# Qwiic_USB_Bridge_ATSAMD21G.net
KiCad netlist of a schematic drawn in EAGLE
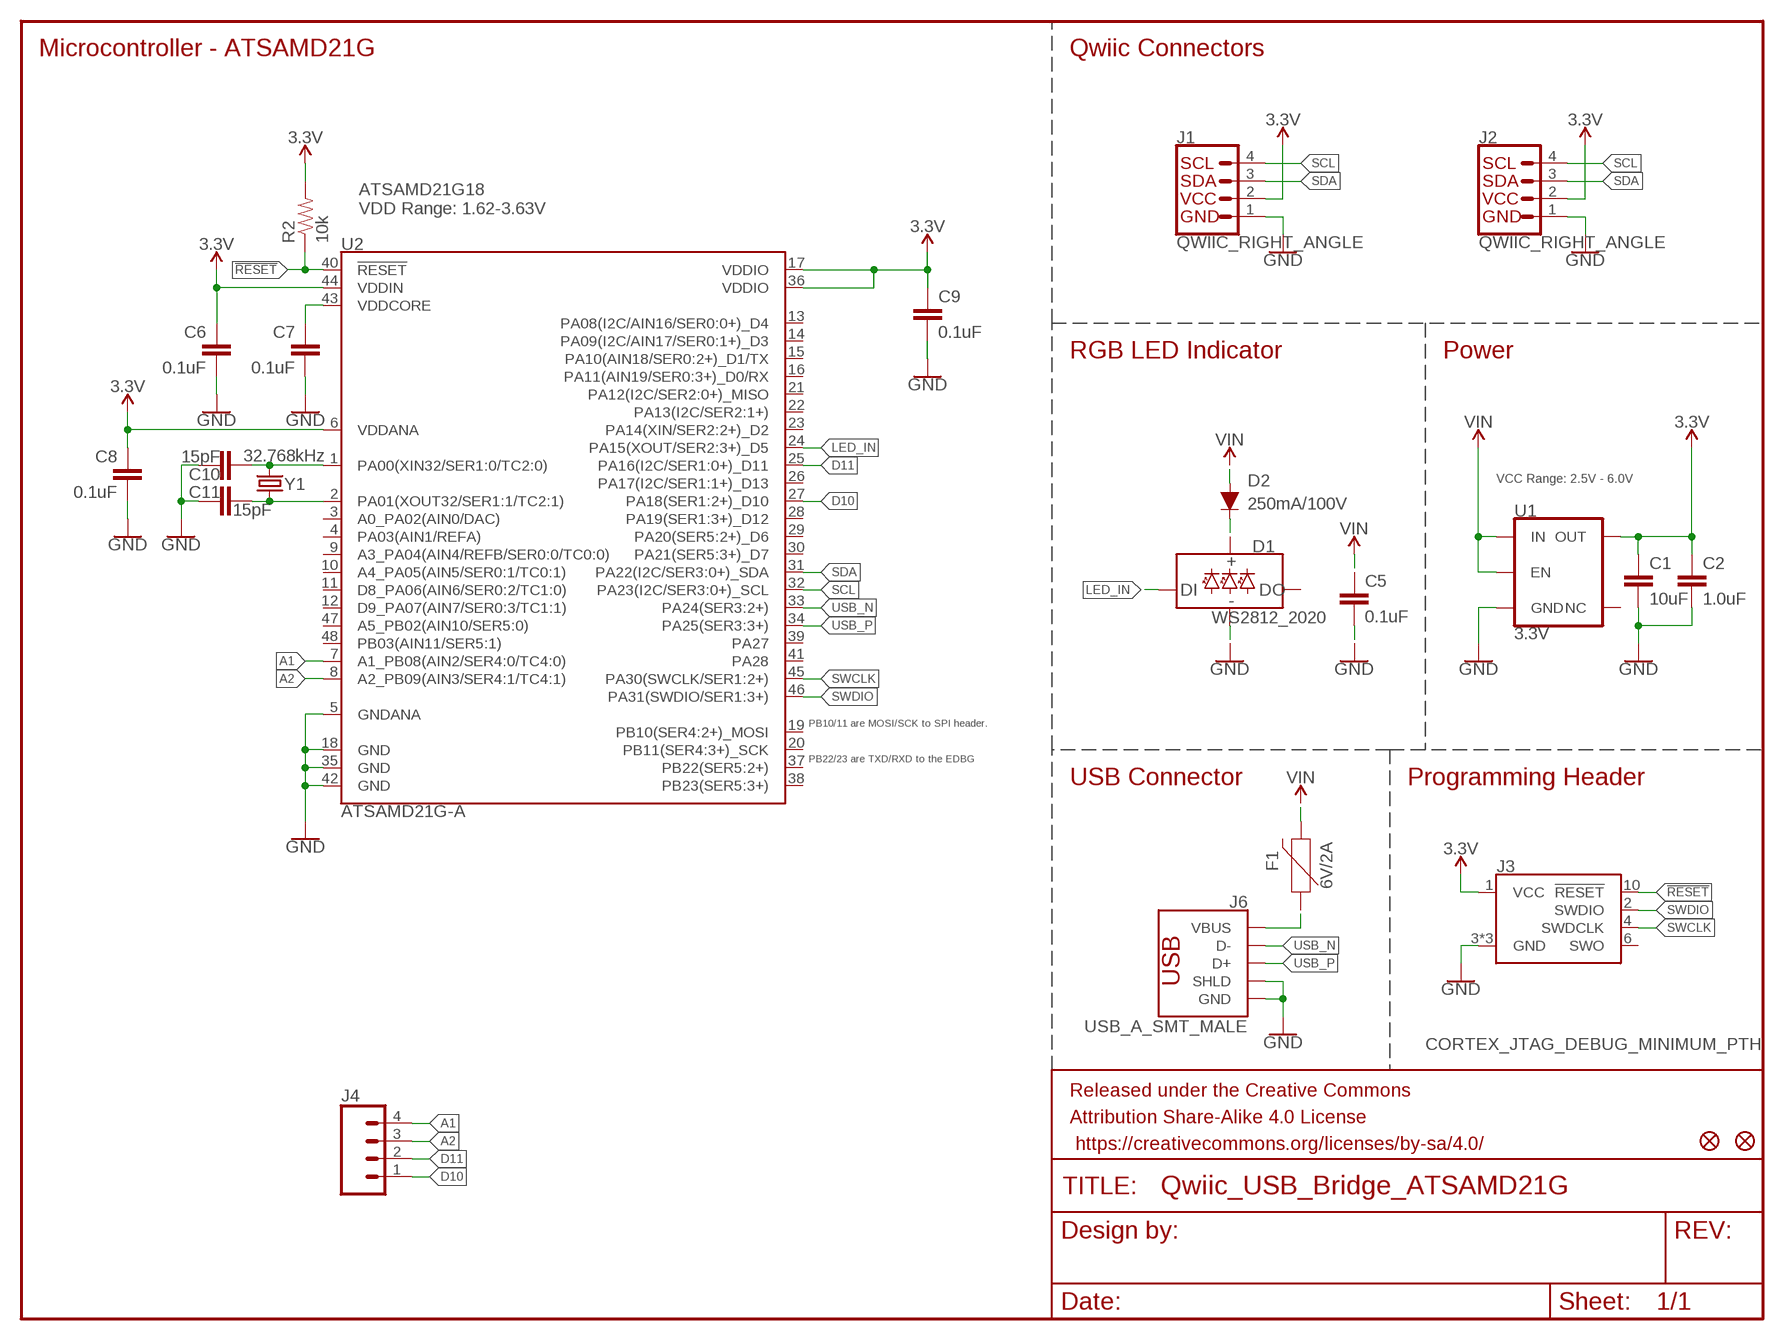
[diagram p0: schematic, sheet 1]

(export (version "E")
  (design (tool "Eeschema 10.0.6"))
  (components
    (comp (ref "C1")
      (value "10uF")
      (footprint "eagle-import:0603")
      (libsource (lib "eagle-import") (part "10UF-0603-6.3V-20%"))
    )
    (comp (ref "C2")
      (value "1.0uF")
      (footprint "eagle-import:0603")
      (libsource (lib "eagle-import") (part "1.0UF-0603-16V-10%"))
    )
    (comp (ref "C5")
      (value "0.1uF")
      (footprint "eagle-import:0603")
      (libsource (lib "eagle-import") (part "0.1UF-0603-25V-(+80/-20%)"))
    )
    (comp (ref "C6")
      (value "0.1uF")
      (footprint "eagle-import:0603")
      (libsource (lib "eagle-import") (part "0.1UF-0603-25V-(+80/-20%)"))
    )
    (comp (ref "C7")
      (value "0.1uF")
      (footprint "eagle-import:0603")
      (libsource (lib "eagle-import") (part "0.1UF-0603-25V-(+80/-20%)"))
    )
    (comp (ref "C8")
      (value "0.1uF")
      (footprint "eagle-import:0603")
      (libsource (lib "eagle-import") (part "0.1UF-0603-25V-(+80/-20%)"))
    )
    (comp (ref "C9")
      (value "0.1uF")
      (footprint "eagle-import:0603")
      (libsource (lib "eagle-import") (part "0.1UF-0603-25V-(+80/-20%)"))
    )
    (comp (ref "C10")
      (value "15pF")
      (footprint "eagle-import:0603")
      (libsource (lib "eagle-import") (part "15PF-0603-50V-5%"))
    )
    (comp (ref "C11")
      (value "15pF")
      (footprint "eagle-import:0603")
      (libsource (lib "eagle-import") (part "15PF-0603-50V-5%"))
    )
    (comp (ref "D1")
      (value "WS2812_2020")
      (footprint "eagle-import:WS2812-2020")
      (libsource (lib "eagle-import") (part "WS2812_2020"))
    )
    (comp (ref "D2")
      (value "250mA/100V")
      (footprint "eagle-import:SOD-323")
      (libsource (lib "eagle-import") (part "DIODE-BAS16J"))
    )
    (comp (ref "F1")
      (value "6V/2A")
      (footprint "eagle-import:1210")
      (libsource (lib "eagle-import") (part "PPTC_6V2A"))
    )
    (comp (ref "FD1")
      (value "FIDUCIALUFIDUCIAL")
      (footprint "eagle-import:FIDUCIAL-MICRO")
      (libsource (lib "eagle-import") (part "FIDUCIALUFIDUCIAL"))
    )
    (comp (ref "FD2")
      (value "FIDUCIALUFIDUCIAL")
      (footprint "eagle-import:FIDUCIAL-MICRO")
      (libsource (lib "eagle-import") (part "FIDUCIALUFIDUCIAL"))
    )
    (comp (ref "FRAME2")
      (value "FRAME-LETTER")
      (footprint "eagle-import:CREATIVE_COMMONS")
      (libsource (lib "eagle-import") (part "FRAME-LETTER"))
    )
    (comp (ref "J1")
      (value "QWIIC_RIGHT_ANGLE")
      (footprint "eagle-import:JST04_1MM_RA")
      (libsource (lib "eagle-import") (part "QWIIC_CONNECTORJS-1MM"))
    )
    (comp (ref "J2")
      (value "QWIIC_RIGHT_ANGLE")
      (footprint "eagle-import:JST04_1MM_RA")
      (libsource (lib "eagle-import") (part "QWIIC_CONNECTORJS-1MM"))
    )
    (comp (ref "J3")
      (value "CORTEX_JTAG_DEBUG_MINIMUM_PTH")
      (footprint "eagle-import:2X5-PTH-1.27MM")
      (libsource (lib "eagle-import") (part "CORTEX_JTAG_DEBUG_MINIMUM_PTH"))
    )
    (comp (ref "J4")
      (value "CONN_041X04_NO_SILK")
      (footprint "eagle-import:1X04_NO_SILK")
      (libsource (lib "eagle-import") (part "CONN_041X04_NO_SILK"))
    )
    (comp (ref "J6")
      (value "USB_A_SMT_MALE")
      (footprint "eagle-import:USB-A-SMT-MALE")
      (libsource (lib "eagle-import") (part "USB_A_SMT_MALE"))
    )
    (comp (ref "R2")
      (value "10k")
      (footprint "eagle-import:0603")
      (libsource (lib "eagle-import") (part "10KOHM-0603-1/10W-1%"))
    )
    (comp (ref "U1")
      (value "3.3V")
      (footprint "eagle-import:SOT23-5")
      (libsource (lib "eagle-import") (part "V_REG_AP2112K-3.3V"))
    )
    (comp (ref "U2")
      (value "ATSAMD21G-A")
      (footprint "eagle-import:TQFP-48")
      (libsource (lib "eagle-import") (part "ATSAMD21G-A"))
    )
    (comp (ref "Y1")
      (value "32.768kHz")
      (footprint "eagle-import:CRYSTAL-SMD-3.2X1.5MM")
      (libsource (lib "eagle-import") (part "CRYSTAL-32.768KHZSMD-3.2X1.5"))
    )
  )
  (nets
    (net (code "1") (name "/~{RESET}") (class "Default")
      (node (ref "J3") (pin "10") (pinfunction "~{RESET}_10") (pintype "bidirectional"))
      (node (ref "R2") (pin "1") (pinfunction "1_1") (pintype "passive"))
      (node (ref "U2") (pin "40") (pinfunction "~{RESET}_40") (pintype "bidirectional"))
    )
    (net (code "2") (name "3.3V") (class "Default")
      (node (ref "C1") (pin "1") (pinfunction "1_1") (pintype "passive"))
      (node (ref "C2") (pin "1") (pinfunction "1_1") (pintype "passive"))
      (node (ref "C6") (pin "1") (pinfunction "1_1") (pintype "passive"))
      (node (ref "C8") (pin "1") (pinfunction "1_1") (pintype "passive"))
      (node (ref "C9") (pin "1") (pinfunction "1_1") (pintype "passive"))
      (node (ref "J1") (pin "2") (pinfunction "2_2") (pintype "power_in"))
      (node (ref "J2") (pin "2") (pinfunction "2_2") (pintype "power_in"))
      (node (ref "J3") (pin "1") (pinfunction "VCC_1") (pintype "bidirectional"))
      (node (ref "R2") (pin "2") (pinfunction "2_2") (pintype "passive"))
      (node (ref "U1") (pin "5") (pinfunction "OUT_5") (pintype "passive"))
      (node (ref "U2") (pin "17") (pinfunction "VDDIO_17") (pintype "bidirectional"))
      (node (ref "U2") (pin "36") (pinfunction "VDDIO_36") (pintype "bidirectional"))
      (node (ref "U2") (pin "44") (pinfunction "VDDIN_44") (pintype "bidirectional"))
      (node (ref "U2") (pin "6") (pinfunction "VDDANA_6") (pintype "bidirectional"))
    )
    (net (code "3") (name "A1") (class "Default")
      (node (ref "J4") (pin "4") (pinfunction "4_4") (pintype "passive"))
      (node (ref "U2") (pin "7") (pinfunction "A1_PB08(AIN2/SER4:0/TC4:0)_7") (pintype "bidirectional"))
    )
    (net (code "4") (name "A2") (class "Default")
      (node (ref "J4") (pin "3") (pinfunction "3_3") (pintype "passive"))
      (node (ref "U2") (pin "8") (pinfunction "A2_PB09(AIN3/SER4:1/TC4:1)_8") (pintype "bidirectional"))
    )
    (net (code "5") (name "D10") (class "Default")
      (node (ref "J4") (pin "1") (pinfunction "1_1") (pintype "passive"))
      (node (ref "U2") (pin "27") (pinfunction "PA18(SER1:2+)_D10_27") (pintype "bidirectional"))
    )
    (net (code "6") (name "D11") (class "Default")
      (node (ref "J4") (pin "2") (pinfunction "2_2") (pintype "passive"))
      (node (ref "U2") (pin "25") (pinfunction "PA16(I2C/SER1:0+)_D11_25") (pintype "bidirectional"))
    )
    (net (code "7") (name "GND") (class "Default")
      (node (ref "C1") (pin "2") (pinfunction "2_2") (pintype "passive"))
      (node (ref "C10") (pin "1") (pinfunction "1_1") (pintype "passive"))
      (node (ref "C11") (pin "2") (pinfunction "2_2") (pintype "passive"))
      (node (ref "C2") (pin "2") (pinfunction "2_2") (pintype "passive"))
      (node (ref "C5") (pin "2") (pinfunction "2_2") (pintype "passive"))
      (node (ref "C6") (pin "2") (pinfunction "2_2") (pintype "passive"))
      (node (ref "C7") (pin "2") (pinfunction "2_2") (pintype "passive"))
      (node (ref "C8") (pin "2") (pinfunction "2_2") (pintype "passive"))
      (node (ref "C9") (pin "2") (pinfunction "2_2") (pintype "passive"))
      (node (ref "D1") (pin "GND") (pinfunction "GND_GND") (pintype "bidirectional"))
      (node (ref "J1") (pin "1") (pinfunction "1_1") (pintype "power_in"))
      (node (ref "J2") (pin "1") (pinfunction "1_1") (pintype "power_in"))
      (node (ref "J3") (pin "3") (pinfunction "GND_3") (pintype "bidirectional"))
      (node (ref "J3") (pin "5") (pinfunction "GND_5") (pintype "bidirectional"))
      (node (ref "J3") (pin "9") (pinfunction "GND_9") (pintype "bidirectional"))
      (node (ref "J6") (pin "GND1") (pinfunction "GND_GND1") (pintype "power_in"))
      (node (ref "J6") (pin "SHLD1") (pinfunction "SHLD_SHLD1") (pintype "bidirectional"))
      (node (ref "J6") (pin "SHLD2") (pinfunction "SHLD_SHLD2") (pintype "bidirectional"))
      (node (ref "U1") (pin "2") (pinfunction "GND_2") (pintype "input"))
      (node (ref "U2") (pin "18") (pinfunction "GND_18") (pintype "bidirectional"))
      (node (ref "U2") (pin "35") (pinfunction "GND_35") (pintype "bidirectional"))
      (node (ref "U2") (pin "42") (pinfunction "GND_42") (pintype "bidirectional"))
      (node (ref "U2") (pin "5") (pinfunction "GNDANA_5") (pintype "bidirectional"))
    )
    (net (code "8") (name "LED_IN") (class "Default")
      (node (ref "D1") (pin "DI") (pinfunction "DI_DI") (pintype "bidirectional"))
      (node (ref "U2") (pin "24") (pinfunction "PA15(XOUT/SER2:3+)_D5_24") (pintype "bidirectional"))
    )
    (net (code "9") (name "Net-(D1-PadVCC)") (class "Default")
      (node (ref "D1") (pin "VCC") (pinfunction "VCC_VCC") (pintype "bidirectional"))
      (node (ref "D2") (pin "C") (pinfunction "C_C") (pintype "passive"))
    )
    (net (code "10") (name "Net-(J6-VBUS)") (class "Default")
      (node (ref "F1") (pin "1") (pinfunction "1_1") (pintype "bidirectional"))
      (node (ref "J6") (pin "VBUS1") (pinfunction "VBUS_VBUS1") (pintype "power_in"))
    )
    (net (code "11") (name "Net-(U2-PA00(XIN32{slash}SER1:0{slash}TC2:0))") (class "Default")
      (node (ref "C10") (pin "2") (pinfunction "2_2") (pintype "passive"))
      (node (ref "U2") (pin "1") (pinfunction "PA00(XIN32/SER1:0/TC2:0)_1") (pintype "bidirectional"))
      (node (ref "Y1") (pin "P$2") (pinfunction "2_P$2") (pintype "passive"))
    )
    (net (code "12") (name "Net-(U2-PA01(XOUT32{slash}SER1:1{slash}TC2:1))") (class "Default")
      (node (ref "C11") (pin "1") (pinfunction "1_1") (pintype "passive"))
      (node (ref "U2") (pin "2") (pinfunction "PA01(XOUT32/SER1:1/TC2:1)_2") (pintype "bidirectional"))
      (node (ref "Y1") (pin "P$1") (pinfunction "1_P$1") (pintype "passive"))
    )
    (net (code "13") (name "Net-(U2-VDDCORE)") (class "Default")
      (node (ref "C7") (pin "1") (pinfunction "1_1") (pintype "passive"))
      (node (ref "U2") (pin "43") (pinfunction "VDDCORE_43") (pintype "bidirectional"))
    )
    (net (code "14") (name "SCL") (class "Default")
      (node (ref "J1") (pin "4") (pinfunction "4_4") (pintype "passive"))
      (node (ref "J2") (pin "4") (pinfunction "4_4") (pintype "passive"))
      (node (ref "U2") (pin "32") (pinfunction "PA23(I2C/SER3:0+)_SCL_32") (pintype "bidirectional"))
    )
    (net (code "15") (name "SDA") (class "Default")
      (node (ref "J1") (pin "3") (pinfunction "3_3") (pintype "passive"))
      (node (ref "J2") (pin "3") (pinfunction "3_3") (pintype "passive"))
      (node (ref "U2") (pin "31") (pinfunction "PA22(I2C/SER3:0+)_SDA_31") (pintype "bidirectional"))
    )
    (net (code "16") (name "SWCLK") (class "Default")
      (node (ref "J3") (pin "4") (pinfunction "SWDCLK_4") (pintype "bidirectional"))
      (node (ref "U2") (pin "45") (pinfunction "PA30(SWCLK/SER1:2+)_45") (pintype "bidirectional"))
    )
    (net (code "17") (name "SWDIO") (class "Default")
      (node (ref "J3") (pin "2") (pinfunction "SWDIO_2") (pintype "bidirectional"))
      (node (ref "U2") (pin "46") (pinfunction "PA31(SWDIO/SER1:3+)_46") (pintype "bidirectional"))
    )
    (net (code "18") (name "USB_N") (class "Default")
      (node (ref "J6") (pin "D-1") (pinfunction "D-_D-1") (pintype "bidirectional"))
      (node (ref "U2") (pin "33") (pinfunction "PA24(SER3:2+)_33") (pintype "bidirectional"))
    )
    (net (code "19") (name "USB_P") (class "Default")
      (node (ref "J6") (pin "D+1") (pinfunction "D+_D+1") (pintype "bidirectional"))
      (node (ref "U2") (pin "34") (pinfunction "PA25(SER3:3+)_34") (pintype "bidirectional"))
    )
    (net (code "20") (name "VIN") (class "Default")
      (node (ref "C5") (pin "1") (pinfunction "1_1") (pintype "passive"))
      (node (ref "D2") (pin "A") (pinfunction "A_A") (pintype "passive"))
      (node (ref "F1") (pin "2") (pinfunction "2_2") (pintype "bidirectional"))
      (node (ref "U1") (pin "1") (pinfunction "IN_1") (pintype "input"))
      (node (ref "U1") (pin "3") (pinfunction "EN_3") (pintype "input"))
    )
    (net (code "21") (name "unconnected-(D1-PadDO)") (class "Default")
      (node (ref "D1") (pin "DO") (pinfunction "DO_DO") (pintype "bidirectional"))
    )
    (net (code "22") (name "unconnected-(J3-SWO-Pad6)") (class "Default")
      (node (ref "J3") (pin "6") (pinfunction "SWO_6") (pintype "bidirectional"))
    )
    (net (code "23") (name "unconnected-(U1-NC-Pad4)") (class "Default")
      (node (ref "U1") (pin "4") (pinfunction "NC_4") (pintype "no_connect"))
    )
    (net (code "24") (name "unconnected-(U2-A0_PA02(AIN0{slash}DAC)-Pad3)") (class "Default")
      (node (ref "U2") (pin "3") (pinfunction "A0_PA02(AIN0/DAC)_3") (pintype "bidirectional"))
    )
    (net (code "25") (name "unconnected-(U2-A3_PA04(AIN4{slash}REFB{slash}SER0:0{slash}TC0:0)-Pad9)") (class "Default")
      (node (ref "U2") (pin "9") (pinfunction "A3_PA04(AIN4/REFB/SER0:0/TC0:0)_9") (pintype "bidirectional"))
    )
    (net (code "26") (name "unconnected-(U2-A4_PA05(AIN5{slash}SER0:1{slash}TC0:1)-Pad10)") (class "Default")
      (node (ref "U2") (pin "10") (pinfunction "A4_PA05(AIN5/SER0:1/TC0:1)_10") (pintype "bidirectional"))
    )
    (net (code "27") (name "unconnected-(U2-A5_PB02(AIN10{slash}SER5:0)-Pad47)") (class "Default")
      (node (ref "U2") (pin "47") (pinfunction "A5_PB02(AIN10/SER5:0)_47") (pintype "bidirectional"))
    )
    (net (code "28") (name "unconnected-(U2-D8_PA06(AIN6{slash}SER0:2{slash}TC1:0)-Pad11)") (class "Default")
      (node (ref "U2") (pin "11") (pinfunction "D8_PA06(AIN6/SER0:2/TC1:0)_11") (pintype "bidirectional"))
    )
    (net (code "29") (name "unconnected-(U2-D9_PA07(AIN7{slash}SER0:3{slash}TC1:1)-Pad12)") (class "Default")
      (node (ref "U2") (pin "12") (pinfunction "D9_PA07(AIN7/SER0:3/TC1:1)_12") (pintype "bidirectional"))
    )
    (net (code "30") (name "unconnected-(U2-PA03(AIN1{slash}REFA)-Pad4)") (class "Default")
      (node (ref "U2") (pin "4") (pinfunction "PA03(AIN1/REFA)_4") (pintype "bidirectional"))
    )
    (net (code "31") (name "unconnected-(U2-PA08(I2C{slash}AIN16{slash}SER0:0+)_D4-Pad13)") (class "Default")
      (node (ref "U2") (pin "13") (pinfunction "PA08(I2C/AIN16/SER0:0+)_D4_13") (pintype "bidirectional"))
    )
    (net (code "32") (name "unconnected-(U2-PA09(I2C{slash}AIN17{slash}SER0:1+)_D3-Pad14)") (class "Default")
      (node (ref "U2") (pin "14") (pinfunction "PA09(I2C/AIN17/SER0:1+)_D3_14") (pintype "bidirectional"))
    )
    (net (code "33") (name "unconnected-(U2-PA10(AIN18{slash}SER0:2+)_D1{slash}TX-Pad15)") (class "Default")
      (node (ref "U2") (pin "15") (pinfunction "PA10(AIN18/SER0:2+)_D1/TX_15") (pintype "bidirectional"))
    )
    (net (code "34") (name "unconnected-(U2-PA11(AIN19{slash}SER0:3+)_D0{slash}RX-Pad16)") (class "Default")
      (node (ref "U2") (pin "16") (pinfunction "PA11(AIN19/SER0:3+)_D0/RX_16") (pintype "bidirectional"))
    )
    (net (code "35") (name "unconnected-(U2-PA12(I2C{slash}SER2:0+)_MISO-Pad21)") (class "Default")
      (node (ref "U2") (pin "21") (pinfunction "PA12(I2C/SER2:0+)_MISO_21") (pintype "bidirectional"))
    )
    (net (code "36") (name "unconnected-(U2-PA13(I2C{slash}SER2:1+)-Pad22)") (class "Default")
      (node (ref "U2") (pin "22") (pinfunction "PA13(I2C/SER2:1+)_22") (pintype "bidirectional"))
    )
    (net (code "37") (name "unconnected-(U2-PA14(XIN{slash}SER2:2+)_D2-Pad23)") (class "Default")
      (node (ref "U2") (pin "23") (pinfunction "PA14(XIN/SER2:2+)_D2_23") (pintype "bidirectional"))
    )
    (net (code "38") (name "unconnected-(U2-PA17(I2C{slash}SER1:1+)_D13-Pad26)") (class "Default")
      (node (ref "U2") (pin "26") (pinfunction "PA17(I2C/SER1:1+)_D13_26") (pintype "bidirectional"))
    )
    (net (code "39") (name "unconnected-(U2-PA19(SER1:3+)_D12-Pad28)") (class "Default")
      (node (ref "U2") (pin "28") (pinfunction "PA19(SER1:3+)_D12_28") (pintype "bidirectional"))
    )
    (net (code "40") (name "unconnected-(U2-PA20(SER5:2+)_D6-Pad29)") (class "Default")
      (node (ref "U2") (pin "29") (pinfunction "PA20(SER5:2+)_D6_29") (pintype "bidirectional"))
    )
    (net (code "41") (name "unconnected-(U2-PA21(SER5:3+)_D7-Pad30)") (class "Default")
      (node (ref "U2") (pin "30") (pinfunction "PA21(SER5:3+)_D7_30") (pintype "bidirectional"))
    )
    (net (code "42") (name "unconnected-(U2-PA27-Pad39)") (class "Default")
      (node (ref "U2") (pin "39") (pinfunction "PA27_39") (pintype "bidirectional"))
    )
    (net (code "43") (name "unconnected-(U2-PA28-Pad41)") (class "Default")
      (node (ref "U2") (pin "41") (pinfunction "PA28_41") (pintype "bidirectional"))
    )
    (net (code "44") (name "unconnected-(U2-PB03(AIN11{slash}SER5:1)-Pad48)") (class "Default")
      (node (ref "U2") (pin "48") (pinfunction "PB03(AIN11/SER5:1)_48") (pintype "bidirectional"))
    )
    (net (code "45") (name "unconnected-(U2-PB10(SER4:2+)_MOSI-Pad19)") (class "Default")
      (node (ref "U2") (pin "19") (pinfunction "PB10(SER4:2+)_MOSI_19") (pintype "bidirectional"))
    )
    (net (code "46") (name "unconnected-(U2-PB11(SER4:3+)_SCK-Pad20)") (class "Default")
      (node (ref "U2") (pin "20") (pinfunction "PB11(SER4:3+)_SCK_20") (pintype "bidirectional"))
    )
    (net (code "47") (name "unconnected-(U2-PB22(SER5:2+)-Pad37)") (class "Default")
      (node (ref "U2") (pin "37") (pinfunction "PB22(SER5:2+)_37") (pintype "bidirectional"))
    )
    (net (code "48") (name "unconnected-(U2-PB23(SER5:3+)-Pad38)") (class "Default")
      (node (ref "U2") (pin "38") (pinfunction "PB23(SER5:3+)_38") (pintype "bidirectional"))
    )
  )
)
